# jmb575.net
KiCad netlist of a schematic drawn in Altium Designer
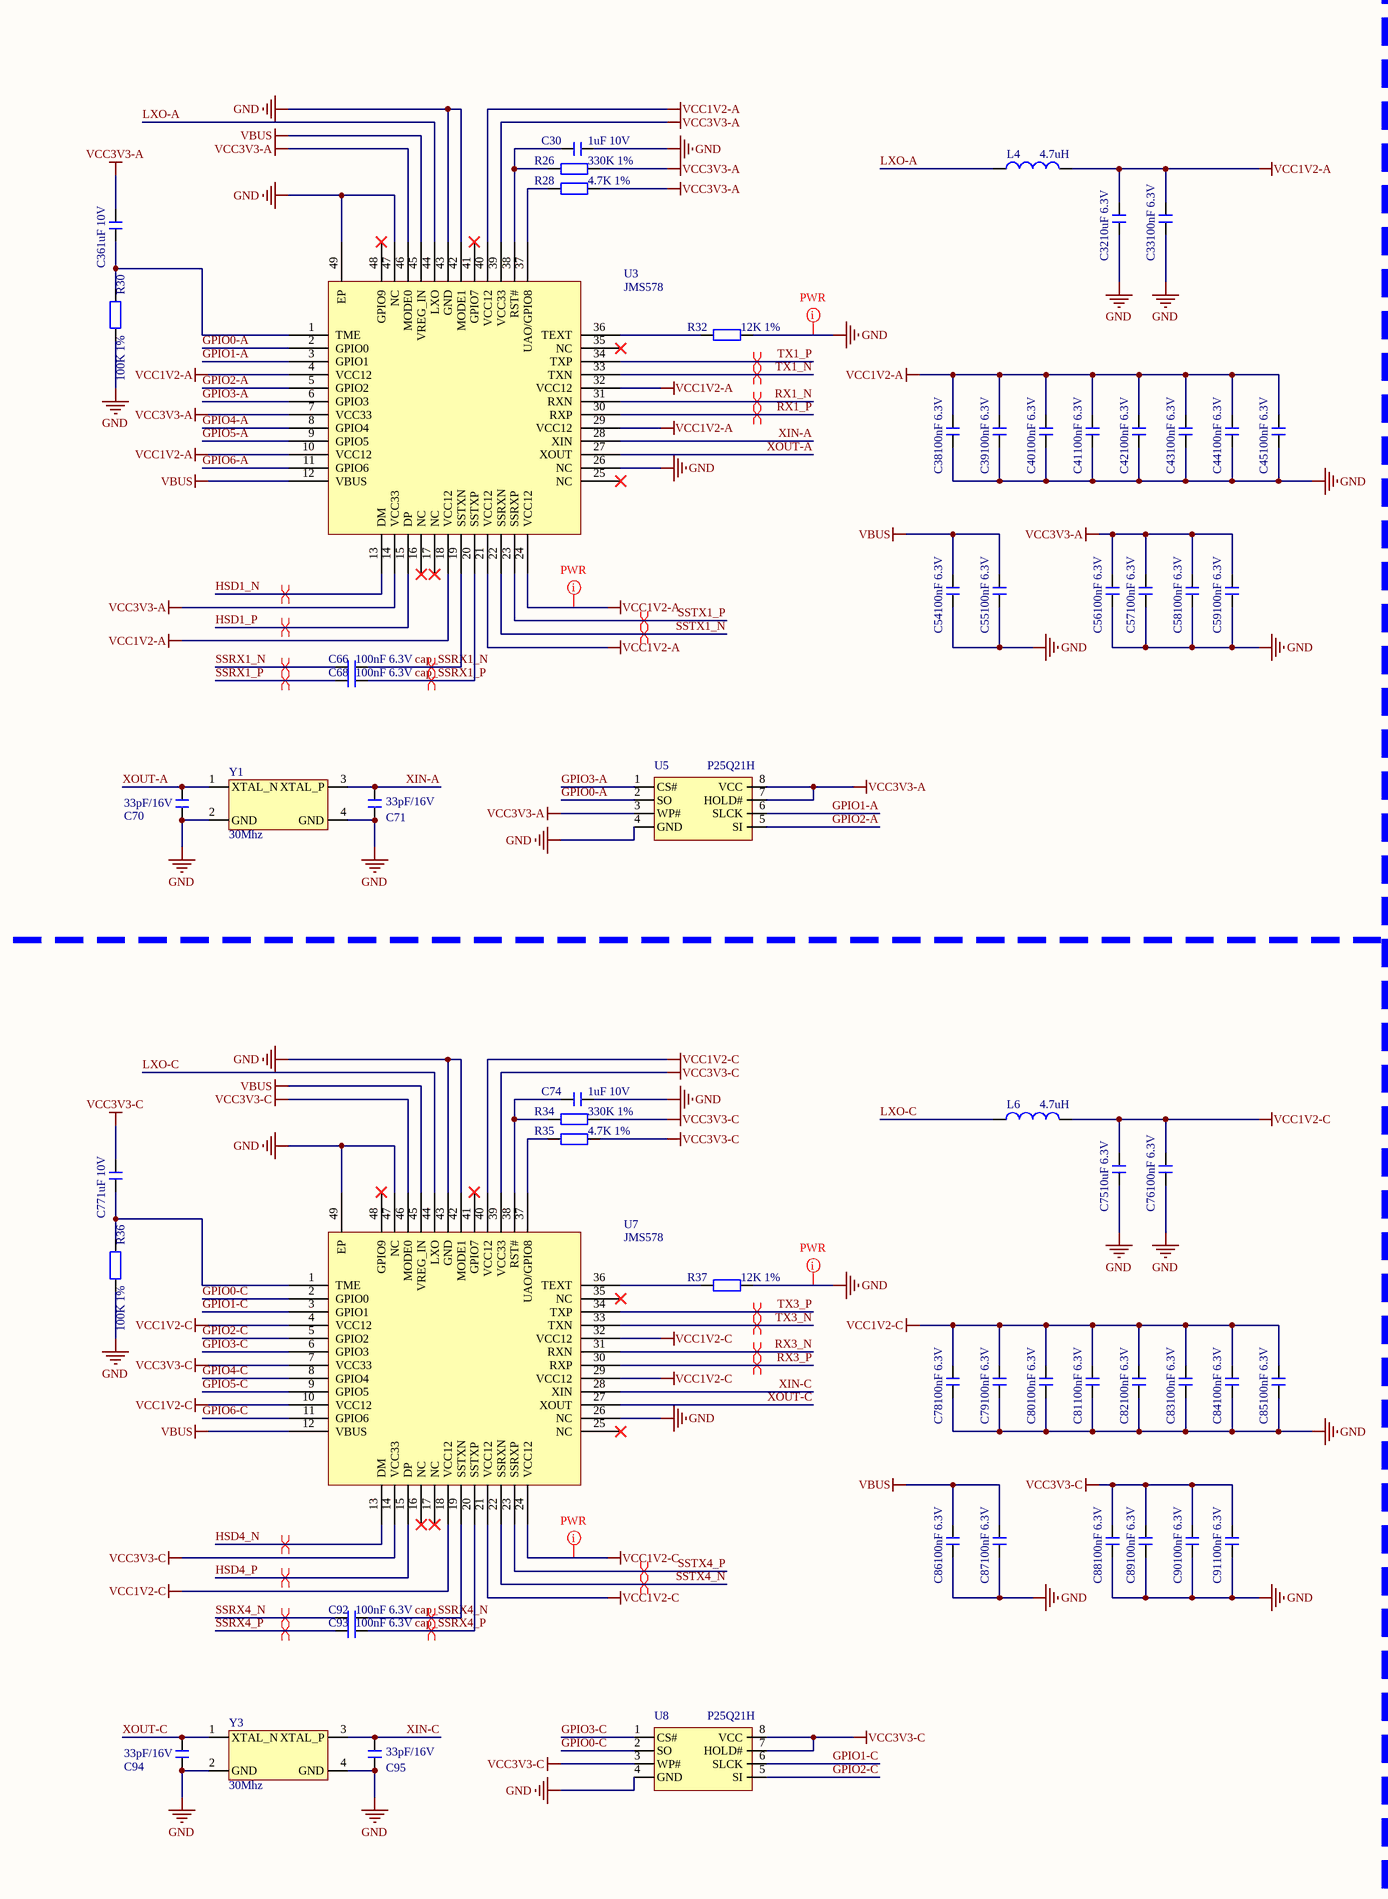
[diagram p0: jmb575.SchDoc, left]
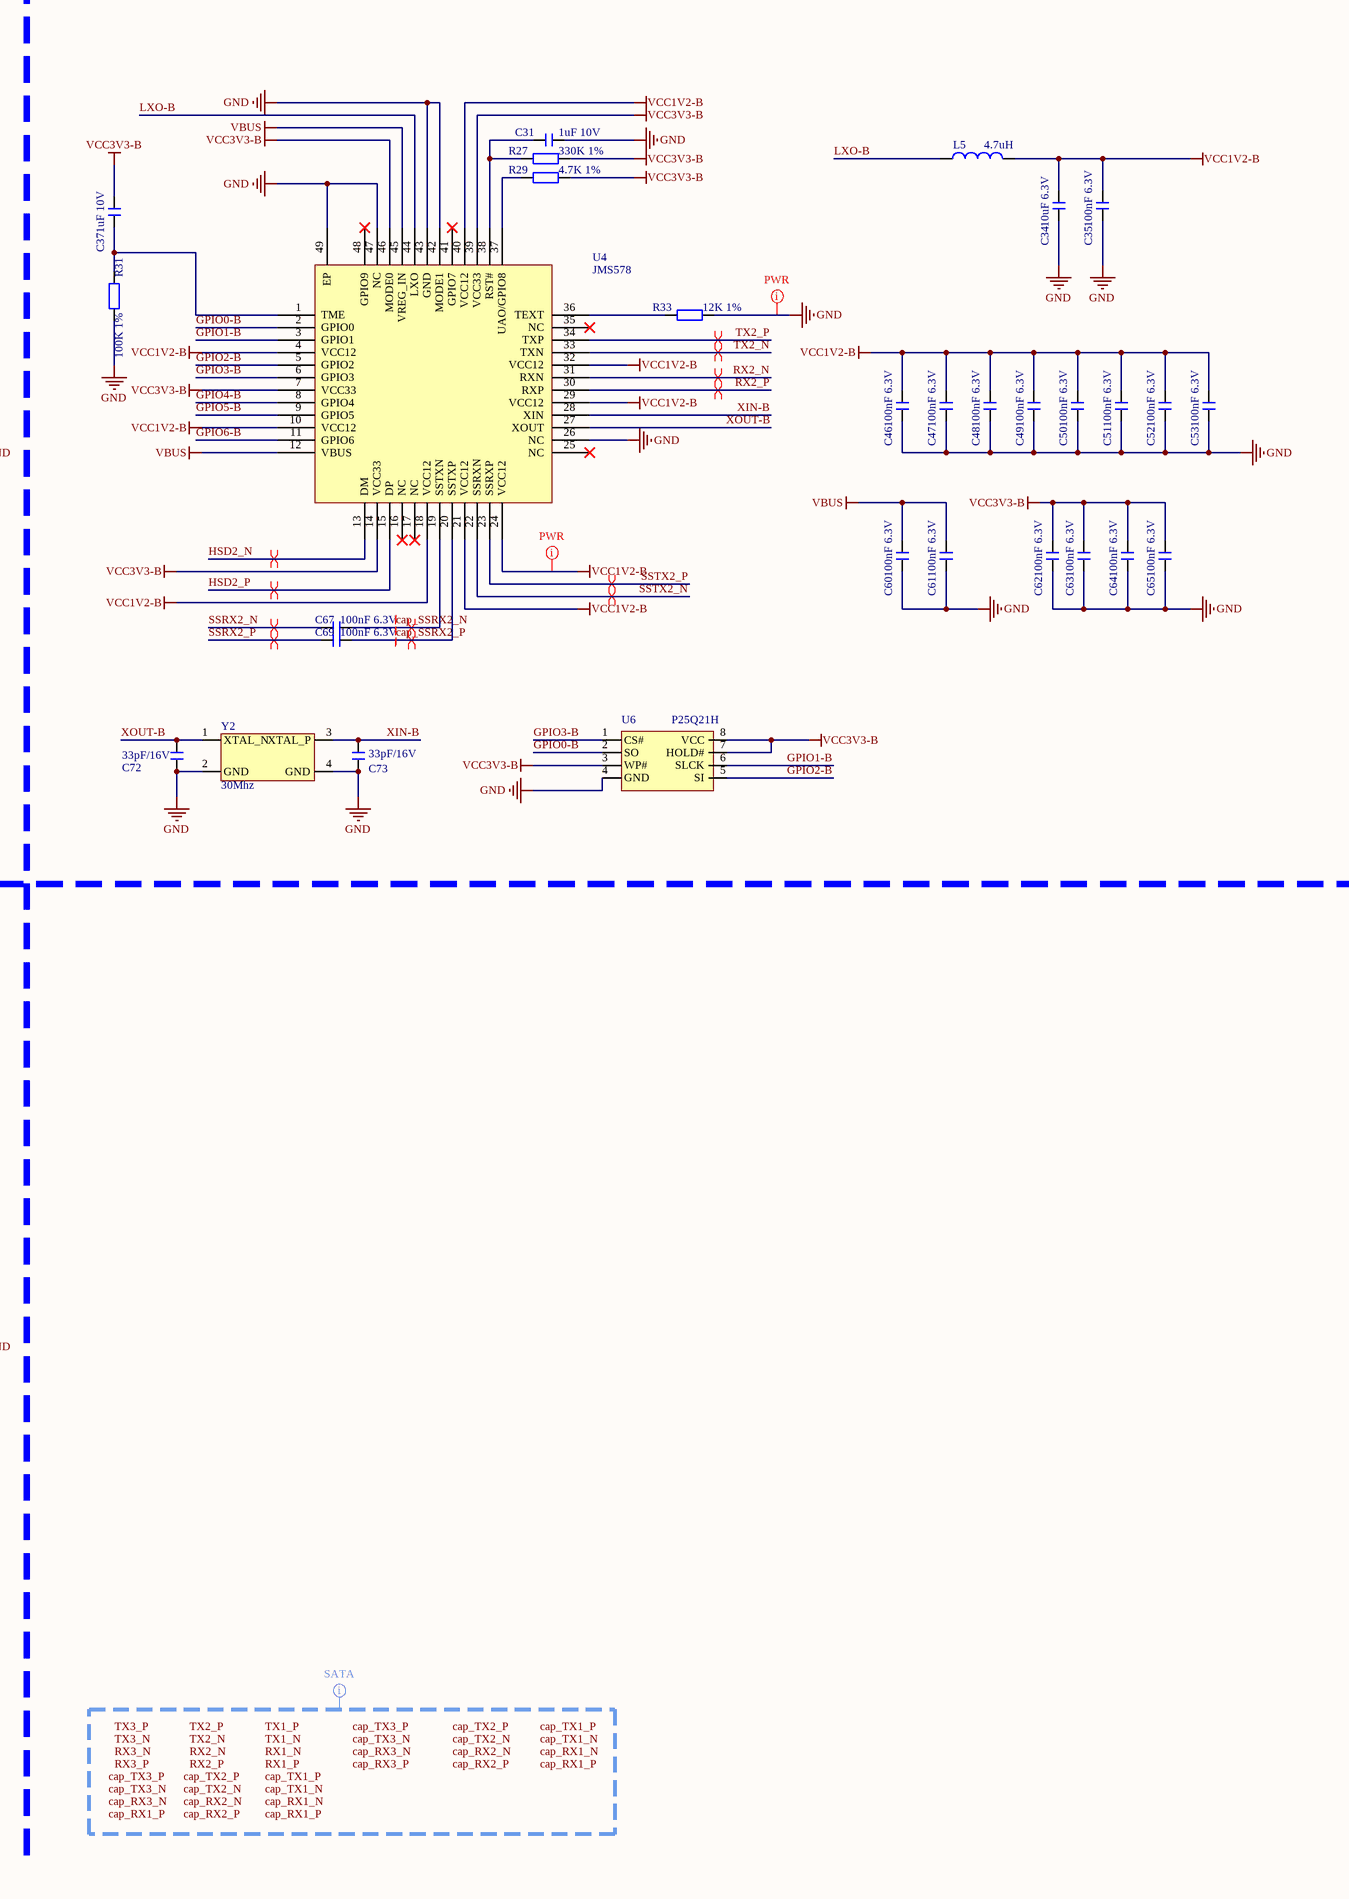
[diagram p1: jmb575.SchDoc, right]

(export (version "E")
  (design (tool "Eeschema 10.0.6"))
  (components
    (comp (ref "C30")
      (value "1uF 10V")
      (footprint "C0402_L")
      (description "无极性贴片电容")
      (fields (field (name "版权归属") "源创客"))
      (libsource (lib "Capacitor") (part "C"))
    )
    (comp (ref "C31")
      (value "1uF 10V")
      (footprint "C0402_L")
      (description "无极性贴片电容")
      (fields (field (name "版权归属") "源创客"))
      (libsource (lib "Capacitor") (part "C"))
    )
    (comp (ref "C32")
      (value "10uF 6.3V")
      (footprint "C0603_L")
      (description "无极性贴片电容")
      (fields (field (name "版权归属") "源创客"))
      (libsource (lib "Capacitor") (part "C"))
    )
    (comp (ref "C33")
      (value "100nF 6.3V")
      (footprint "C0402_L")
      (description "无极性贴片电容")
      (fields (field (name "版权归属") "源创客"))
      (libsource (lib "Capacitor") (part "C"))
    )
    (comp (ref "C34")
      (value "10uF 6.3V")
      (footprint "C0603_L")
      (description "无极性贴片电容")
      (fields (field (name "版权归属") "源创客"))
      (libsource (lib "Capacitor") (part "C"))
    )
    (comp (ref "C35")
      (value "100nF 6.3V")
      (footprint "C0402_L")
      (description "无极性贴片电容")
      (fields (field (name "版权归属") "源创客"))
      (libsource (lib "Capacitor") (part "C"))
    )
    (comp (ref "C36")
      (value "1uF 10V")
      (footprint "C0402_L")
      (description "无极性贴片电容")
      (fields (field (name "版权归属") "源创客"))
      (libsource (lib "Capacitor") (part "C"))
    )
    (comp (ref "C37")
      (value "1uF 10V")
      (footprint "C0402_L")
      (description "无极性贴片电容")
      (fields (field (name "版权归属") "源创客"))
      (libsource (lib "Capacitor") (part "C"))
    )
    (comp (ref "C38")
      (value "100nF 6.3V")
      (footprint "C0402_L")
      (description "无极性贴片电容")
      (fields (field (name "版权归属") "源创客"))
      (libsource (lib "Capacitor") (part "C"))
    )
    (comp (ref "C39")
      (value "100nF 6.3V")
      (footprint "C0402_L")
      (description "无极性贴片电容")
      (fields (field (name "版权归属") "源创客"))
      (libsource (lib "Capacitor") (part "C"))
    )
    (comp (ref "C40")
      (value "100nF 6.3V")
      (footprint "C0402_L")
      (description "无极性贴片电容")
      (fields (field (name "版权归属") "源创客"))
      (libsource (lib "Capacitor") (part "C"))
    )
    (comp (ref "C41")
      (value "100nF 6.3V")
      (footprint "C0402_L")
      (description "无极性贴片电容")
      (fields (field (name "版权归属") "源创客"))
      (libsource (lib "Capacitor") (part "C"))
    )
    (comp (ref "C42")
      (value "100nF 6.3V")
      (footprint "C0402_L")
      (description "无极性贴片电容")
      (fields (field (name "版权归属") "源创客"))
      (libsource (lib "Capacitor") (part "C"))
    )
    (comp (ref "C43")
      (value "100nF 6.3V")
      (footprint "C0402_L")
      (description "无极性贴片电容")
      (fields (field (name "版权归属") "源创客"))
      (libsource (lib "Capacitor") (part "C"))
    )
    (comp (ref "C44")
      (value "100nF 6.3V")
      (footprint "C0402_L")
      (description "无极性贴片电容")
      (fields (field (name "版权归属") "源创客"))
      (libsource (lib "Capacitor") (part "C"))
    )
    (comp (ref "C45")
      (value "100nF 6.3V")
      (footprint "C0402_L")
      (description "无极性贴片电容")
      (fields (field (name "版权归属") "源创客"))
      (libsource (lib "Capacitor") (part "C"))
    )
    (comp (ref "C46")
      (value "100nF 6.3V")
      (footprint "C0402_L")
      (description "无极性贴片电容")
      (fields (field (name "版权归属") "源创客"))
      (libsource (lib "Capacitor") (part "C"))
    )
    (comp (ref "C47")
      (value "100nF 6.3V")
      (footprint "C0402_L")
      (description "无极性贴片电容")
      (fields (field (name "版权归属") "源创客"))
      (libsource (lib "Capacitor") (part "C"))
    )
    (comp (ref "C48")
      (value "100nF 6.3V")
      (footprint "C0402_L")
      (description "无极性贴片电容")
      (fields (field (name "版权归属") "源创客"))
      (libsource (lib "Capacitor") (part "C"))
    )
    (comp (ref "C49")
      (value "100nF 6.3V")
      (footprint "C0402_L")
      (description "无极性贴片电容")
      (fields (field (name "版权归属") "源创客"))
      (libsource (lib "Capacitor") (part "C"))
    )
    (comp (ref "C50")
      (value "100nF 6.3V")
      (footprint "C0402_L")
      (description "无极性贴片电容")
      (fields (field (name "版权归属") "源创客"))
      (libsource (lib "Capacitor") (part "C"))
    )
    (comp (ref "C51")
      (value "100nF 6.3V")
      (footprint "C0402_L")
      (description "无极性贴片电容")
      (fields (field (name "版权归属") "源创客"))
      (libsource (lib "Capacitor") (part "C"))
    )
    (comp (ref "C52")
      (value "100nF 6.3V")
      (footprint "C0402_L")
      (description "无极性贴片电容")
      (fields (field (name "版权归属") "源创客"))
      (libsource (lib "Capacitor") (part "C"))
    )
    (comp (ref "C53")
      (value "100nF 6.3V")
      (footprint "C0402_L")
      (description "无极性贴片电容")
      (fields (field (name "版权归属") "源创客"))
      (libsource (lib "Capacitor") (part "C"))
    )
    (comp (ref "C54")
      (value "100nF 6.3V")
      (footprint "C0402_L")
      (description "无极性贴片电容")
      (fields (field (name "版权归属") "源创客"))
      (libsource (lib "Capacitor") (part "C"))
    )
    (comp (ref "C55")
      (value "100nF 6.3V")
      (footprint "C0402_L")
      (description "无极性贴片电容")
      (fields (field (name "版权归属") "源创客"))
      (libsource (lib "Capacitor") (part "C"))
    )
    (comp (ref "C56")
      (value "100nF 6.3V")
      (footprint "C0402_L")
      (description "无极性贴片电容")
      (fields (field (name "版权归属") "源创客"))
      (libsource (lib "Capacitor") (part "C"))
    )
    (comp (ref "C57")
      (value "100nF 6.3V")
      (footprint "C0402_L")
      (description "无极性贴片电容")
      (fields (field (name "版权归属") "源创客"))
      (libsource (lib "Capacitor") (part "C"))
    )
    (comp (ref "C58")
      (value "100nF 6.3V")
      (footprint "C0402_L")
      (description "无极性贴片电容")
      (fields (field (name "版权归属") "源创客"))
      (libsource (lib "Capacitor") (part "C"))
    )
    (comp (ref "C59")
      (value "100nF 6.3V")
      (footprint "C0402_L")
      (description "无极性贴片电容")
      (fields (field (name "版权归属") "源创客"))
      (libsource (lib "Capacitor") (part "C"))
    )
    (comp (ref "C60")
      (value "100nF 6.3V")
      (footprint "C0402_L")
      (description "无极性贴片电容")
      (fields (field (name "版权归属") "源创客"))
      (libsource (lib "Capacitor") (part "C"))
    )
    (comp (ref "C61")
      (value "100nF 6.3V")
      (footprint "C0402_L")
      (description "无极性贴片电容")
      (fields (field (name "版权归属") "源创客"))
      (libsource (lib "Capacitor") (part "C"))
    )
    (comp (ref "C62")
      (value "100nF 6.3V")
      (footprint "C0402_L")
      (description "无极性贴片电容")
      (fields (field (name "版权归属") "源创客"))
      (libsource (lib "Capacitor") (part "C"))
    )
    (comp (ref "C63")
      (value "100nF 6.3V")
      (footprint "C0402_L")
      (description "无极性贴片电容")
      (fields (field (name "版权归属") "源创客"))
      (libsource (lib "Capacitor") (part "C"))
    )
    (comp (ref "C64")
      (value "100nF 6.3V")
      (footprint "C0402_L")
      (description "无极性贴片电容")
      (fields (field (name "版权归属") "源创客"))
      (libsource (lib "Capacitor") (part "C"))
    )
    (comp (ref "C65")
      (value "100nF 6.3V")
      (footprint "C0402_L")
      (description "无极性贴片电容")
      (fields (field (name "版权归属") "源创客"))
      (libsource (lib "Capacitor") (part "C"))
    )
    (comp (ref "C66")
      (value "100nF 6.3V")
      (footprint "C0402_L")
      (description "无极性贴片电容")
      (fields (field (name "版权归属") "源创客"))
      (libsource (lib "Capacitor") (part "C"))
    )
    (comp (ref "C67")
      (value "100nF 6.3V")
      (footprint "C0402_L")
      (description "无极性贴片电容")
      (fields (field (name "版权归属") "源创客"))
      (libsource (lib "Capacitor") (part "C"))
    )
    (comp (ref "C68")
      (value "100nF 6.3V")
      (footprint "C0402_L")
      (description "无极性贴片电容")
      (fields (field (name "版权归属") "源创客"))
      (libsource (lib "Capacitor") (part "C"))
    )
    (comp (ref "C69")
      (value "100nF 6.3V")
      (footprint "C0402_L")
      (description "无极性贴片电容")
      (fields (field (name "版权归属") "源创客"))
      (libsource (lib "Capacitor") (part "C"))
    )
    (comp (ref "C70")
      (value "33pF/16V")
      (footprint "C0402_L")
      (description "无极性贴片电容")
      (fields (field (name "版权归属") "源创客"))
      (libsource (lib "Capacitor") (part "C"))
    )
    (comp (ref "C71")
      (value "33pF/16V")
      (footprint "C0402_L")
      (description "无极性贴片电容")
      (fields (field (name "版权归属") "源创客"))
      (libsource (lib "Capacitor") (part "C"))
    )
    (comp (ref "C72")
      (value "33pF/16V")
      (footprint "C0402_L")
      (description "无极性贴片电容")
      (fields (field (name "版权归属") "源创客"))
      (libsource (lib "Capacitor") (part "C"))
    )
    (comp (ref "C73")
      (value "33pF/16V")
      (footprint "C0402_L")
      (description "无极性贴片电容")
      (fields (field (name "版权归属") "源创客"))
      (libsource (lib "Capacitor") (part "C"))
    )
    (comp (ref "C74")
      (value "1uF 10V")
      (footprint "C0402_L")
      (description "无极性贴片电容")
      (fields (field (name "版权归属") "源创客"))
      (libsource (lib "Capacitor") (part "C"))
    )
    (comp (ref "C75")
      (value "10uF 6.3V")
      (footprint "C0603_L")
      (description "无极性贴片电容")
      (fields (field (name "版权归属") "源创客"))
      (libsource (lib "Capacitor") (part "C"))
    )
    (comp (ref "C76")
      (value "100nF 6.3V")
      (footprint "C0402_L")
      (description "无极性贴片电容")
      (fields (field (name "版权归属") "源创客"))
      (libsource (lib "Capacitor") (part "C"))
    )
    (comp (ref "C77")
      (value "1uF 10V")
      (footprint "C0402_L")
      (description "无极性贴片电容")
      (fields (field (name "版权归属") "源创客"))
      (libsource (lib "Capacitor") (part "C"))
    )
    (comp (ref "C78")
      (value "100nF 6.3V")
      (footprint "C0402_L")
      (description "无极性贴片电容")
      (fields (field (name "版权归属") "源创客"))
      (libsource (lib "Capacitor") (part "C"))
    )
    (comp (ref "C79")
      (value "100nF 6.3V")
      (footprint "C0402_L")
      (description "无极性贴片电容")
      (fields (field (name "版权归属") "源创客"))
      (libsource (lib "Capacitor") (part "C"))
    )
    (comp (ref "C80")
      (value "100nF 6.3V")
      (footprint "C0402_L")
      (description "无极性贴片电容")
      (fields (field (name "版权归属") "源创客"))
      (libsource (lib "Capacitor") (part "C"))
    )
    (comp (ref "C81")
      (value "100nF 6.3V")
      (footprint "C0402_L")
      (description "无极性贴片电容")
      (fields (field (name "版权归属") "源创客"))
      (libsource (lib "Capacitor") (part "C"))
    )
    (comp (ref "C82")
      (value "100nF 6.3V")
      (footprint "C0402_L")
      (description "无极性贴片电容")
      (fields (field (name "版权归属") "源创客"))
      (libsource (lib "Capacitor") (part "C"))
    )
    (comp (ref "C83")
      (value "100nF 6.3V")
      (footprint "C0402_L")
      (description "无极性贴片电容")
      (fields (field (name "版权归属") "源创客"))
      (libsource (lib "Capacitor") (part "C"))
    )
    (comp (ref "C84")
      (value "100nF 6.3V")
      (footprint "C0402_L")
      (description "无极性贴片电容")
      (fields (field (name "版权归属") "源创客"))
      (libsource (lib "Capacitor") (part "C"))
    )
    (comp (ref "C85")
      (value "100nF 6.3V")
      (footprint "C0402_L")
      (description "无极性贴片电容")
      (fields (field (name "版权归属") "源创客"))
      (libsource (lib "Capacitor") (part "C"))
    )
    (comp (ref "C86")
      (value "100nF 6.3V")
      (footprint "C0402_L")
      (description "无极性贴片电容")
      (fields (field (name "版权归属") "源创客"))
      (libsource (lib "Capacitor") (part "C"))
    )
    (comp (ref "C87")
      (value "100nF 6.3V")
      (footprint "C0402_L")
      (description "无极性贴片电容")
      (fields (field (name "版权归属") "源创客"))
      (libsource (lib "Capacitor") (part "C"))
    )
    (comp (ref "C88")
      (value "100nF 6.3V")
      (footprint "C0402_L")
      (description "无极性贴片电容")
      (fields (field (name "版权归属") "源创客"))
      (libsource (lib "Capacitor") (part "C"))
    )
    (comp (ref "C89")
      (value "100nF 6.3V")
      (footprint "C0402_L")
      (description "无极性贴片电容")
      (fields (field (name "版权归属") "源创客"))
      (libsource (lib "Capacitor") (part "C"))
    )
    (comp (ref "C90")
      (value "100nF 6.3V")
      (footprint "C0402_L")
      (description "无极性贴片电容")
      (fields (field (name "版权归属") "源创客"))
      (libsource (lib "Capacitor") (part "C"))
    )
    (comp (ref "C91")
      (value "100nF 6.3V")
      (footprint "C0402_L")
      (description "无极性贴片电容")
      (fields (field (name "版权归属") "源创客"))
      (libsource (lib "Capacitor") (part "C"))
    )
    (comp (ref "C92")
      (value "100nF 6.3V")
      (footprint "C0402_L")
      (description "无极性贴片电容")
      (fields (field (name "版权归属") "源创客"))
      (libsource (lib "Capacitor") (part "C"))
    )
    (comp (ref "C93")
      (value "100nF 6.3V")
      (footprint "C0402_L")
      (description "无极性贴片电容")
      (fields (field (name "版权归属") "源创客"))
      (libsource (lib "Capacitor") (part "C"))
    )
    (comp (ref "C94")
      (value "33pF/16V")
      (footprint "C0402_L")
      (description "无极性贴片电容")
      (fields (field (name "版权归属") "源创客"))
      (libsource (lib "Capacitor") (part "C"))
    )
    (comp (ref "C95")
      (value "33pF/16V")
      (footprint "C0402_L")
      (description "无极性贴片电容")
      (fields (field (name "版权归属") "源创客"))
      (libsource (lib "Capacitor") (part "C"))
    )
    (comp (ref "L4")
      (value "4.7uH")
      (footprint "SMMS0420")
      (description "小功率贴片电感")
      (fields (field (name "版权归属") "源创客"))
      (libsource (lib "Inductor") (part "L"))
    )
    (comp (ref "L5")
      (value "4.7uH")
      (footprint "SMMS0420")
      (description "小功率贴片电感")
      (fields (field (name "版权归属") "源创客"))
      (libsource (lib "Inductor") (part "L"))
    )
    (comp (ref "L6")
      (value "4.7uH")
      (footprint "SMMS0420")
      (description "小功率贴片电感")
      (fields (field (name "版权归属") "源创客"))
      (libsource (lib "Inductor") (part "L"))
    )
    (comp (ref "R26")
      (value "330K 1%")
      (footprint "R0402_L")
      (description "贴片电阻")
      (fields (field (name "版权归属") "源创客"))
      (libsource (lib "Resistor") (part "R"))
    )
    (comp (ref "R27")
      (value "330K 1%")
      (footprint "R0402_L")
      (description "贴片电阻")
      (fields (field (name "版权归属") "源创客"))
      (libsource (lib "Resistor") (part "R"))
    )
    (comp (ref "R28")
      (value "4.7K 1%")
      (footprint "R0402_L")
      (description "贴片电阻")
      (fields (field (name "版权归属") "源创客"))
      (libsource (lib "Resistor") (part "R"))
    )
    (comp (ref "R29")
      (value "4.7K 1%")
      (footprint "R0402_L")
      (description "贴片电阻")
      (fields (field (name "版权归属") "源创客"))
      (libsource (lib "Resistor") (part "R"))
    )
    (comp (ref "R30")
      (value "100K 1%")
      (footprint "R0402_L")
      (description "贴片电阻")
      (fields (field (name "版权归属") "源创客"))
      (libsource (lib "Resistor") (part "R"))
    )
    (comp (ref "R31")
      (value "100K 1%")
      (footprint "R0402_L")
      (description "贴片电阻")
      (fields (field (name "版权归属") "源创客"))
      (libsource (lib "Resistor") (part "R"))
    )
    (comp (ref "R32")
      (value "12K 1%")
      (footprint "R0402_L")
      (description "贴片电阻")
      (fields (field (name "版权归属") "源创客"))
      (libsource (lib "Resistor") (part "R"))
    )
    (comp (ref "R33")
      (value "12K 1%")
      (footprint "R0402_L")
      (description "贴片电阻")
      (fields (field (name "版权归属") "源创客"))
      (libsource (lib "Resistor") (part "R"))
    )
    (comp (ref "R34")
      (value "330K 1%")
      (footprint "R0402_L")
      (description "贴片电阻")
      (fields (field (name "版权归属") "源创客"))
      (libsource (lib "Resistor") (part "R"))
    )
    (comp (ref "R35")
      (value "4.7K 1%")
      (footprint "R0402_L")
      (description "贴片电阻")
      (fields (field (name "版权归属") "源创客"))
      (libsource (lib "Resistor") (part "R"))
    )
    (comp (ref "R36")
      (value "100K 1%")
      (footprint "R0402_L")
      (description "贴片电阻")
      (fields (field (name "版权归属") "源创客"))
      (libsource (lib "Resistor") (part "R"))
    )
    (comp (ref "R37")
      (value "12K 1%")
      (footprint "R0402_L")
      (description "贴片电阻")
      (fields (field (name "版权归属") "源创客"))
      (libsource (lib "Resistor") (part "R"))
    )
    (comp (ref "U3")
      (value "JMS578")
      (footprint "QFN48-L6.0-W6.0-P0.4")
      (libsource (lib "Brage") (part "JMS578"))
    )
    (comp (ref "U4")
      (value "JMS578")
      (footprint "QFN48-L6.0-W6.0-P0.4")
      (libsource (lib "Brage") (part "JMS578"))
    )
    (comp (ref "U5") (value "P25Q21H") (footprint "SOP8_L") (libsource (lib "Flash") (part "P25D40H")))
    (comp (ref "U6") (value "P25Q21H") (footprint "SOP8_L") (libsource (lib "Flash") (part "P25D40H")))
    (comp (ref "U7")
      (value "JMS578")
      (footprint "QFN48-L6.0-W6.0-P0.4")
      (libsource (lib "Brage") (part "JMS578"))
    )
    (comp (ref "U8") (value "P25Q21H") (footprint "SOP8_L") (libsource (lib "Flash") (part "P25D40H")))
    (comp (ref "Y1") (value "30Mhz") (footprint "OSC 3225-4P") (libsource (lib "Crystal") (part "Crystal")))
    (comp (ref "Y2") (value "30Mhz") (footprint "OSC 3225-4P") (libsource (lib "Crystal") (part "Crystal")))
    (comp (ref "Y3") (value "30Mhz") (footprint "OSC 3225-4P") (libsource (lib "Crystal") (part "Crystal")))
  )
  (nets
    (net (code "1") (name "/GPIO0-A") (class "Default")
      (node (ref "U3") (pin "2") (pinfunction "GPIO0_2") (pintype "passive"))
      (node (ref "U5") (pin "2") (pinfunction "SO_2") (pintype "passive"))
    )
    (net (code "2") (name "/GPIO0-B") (class "Default")
      (node (ref "U4") (pin "2") (pinfunction "GPIO0_2") (pintype "passive"))
      (node (ref "U6") (pin "2") (pinfunction "SO_2") (pintype "passive"))
    )
    (net (code "3") (name "/GPIO0-C") (class "Default")
      (node (ref "U7") (pin "2") (pinfunction "GPIO0_2") (pintype "passive"))
      (node (ref "U8") (pin "2") (pinfunction "SO_2") (pintype "passive"))
    )
    (net (code "4") (name "/GPIO1-A") (class "Default")
      (node (ref "U3") (pin "3") (pinfunction "GPIO1_3") (pintype "passive"))
      (node (ref "U5") (pin "6") (pinfunction "SLCK_6") (pintype "passive"))
    )
    (net (code "5") (name "/GPIO1-B") (class "Default")
      (node (ref "U4") (pin "3") (pinfunction "GPIO1_3") (pintype "passive"))
      (node (ref "U6") (pin "6") (pinfunction "SLCK_6") (pintype "passive"))
    )
    (net (code "6") (name "/GPIO1-C") (class "Default")
      (node (ref "U7") (pin "3") (pinfunction "GPIO1_3") (pintype "passive"))
      (node (ref "U8") (pin "6") (pinfunction "SLCK_6") (pintype "passive"))
    )
    (net (code "7") (name "/GPIO2-A") (class "Default")
      (node (ref "U3") (pin "5") (pinfunction "GPIO2_5") (pintype "passive"))
      (node (ref "U5") (pin "5") (pinfunction "SI_5") (pintype "passive"))
    )
    (net (code "8") (name "/GPIO2-B") (class "Default")
      (node (ref "U4") (pin "5") (pinfunction "GPIO2_5") (pintype "passive"))
      (node (ref "U6") (pin "5") (pinfunction "SI_5") (pintype "passive"))
    )
    (net (code "9") (name "/GPIO2-C") (class "Default")
      (node (ref "U7") (pin "5") (pinfunction "GPIO2_5") (pintype "passive"))
      (node (ref "U8") (pin "5") (pinfunction "SI_5") (pintype "passive"))
    )
    (net (code "10") (name "/GPIO3-A") (class "Default")
      (node (ref "U3") (pin "6") (pinfunction "GPIO3_6") (pintype "passive"))
      (node (ref "U5") (pin "1") (pinfunction "CS#_1") (pintype "passive"))
    )
    (net (code "11") (name "/GPIO3-B") (class "Default")
      (node (ref "U4") (pin "6") (pinfunction "GPIO3_6") (pintype "passive"))
      (node (ref "U6") (pin "1") (pinfunction "CS#_1") (pintype "passive"))
    )
    (net (code "12") (name "/GPIO3-C") (class "Default")
      (node (ref "U7") (pin "6") (pinfunction "GPIO3_6") (pintype "passive"))
      (node (ref "U8") (pin "1") (pinfunction "CS#_1") (pintype "passive"))
    )
    (net (code "13") (name "/GPIO4-A") (class "Default")
      (node (ref "U3") (pin "8") (pinfunction "GPIO4_8") (pintype "passive"))
    )
    (net (code "14") (name "/GPIO4-B") (class "Default")
      (node (ref "U4") (pin "8") (pinfunction "GPIO4_8") (pintype "passive"))
    )
    (net (code "15") (name "/GPIO4-C") (class "Default")
      (node (ref "U7") (pin "8") (pinfunction "GPIO4_8") (pintype "passive"))
    )
    (net (code "16") (name "/GPIO5-A") (class "Default")
      (node (ref "U3") (pin "9") (pinfunction "GPIO5_9") (pintype "passive"))
    )
    (net (code "17") (name "/GPIO5-B") (class "Default")
      (node (ref "U4") (pin "9") (pinfunction "GPIO5_9") (pintype "passive"))
    )
    (net (code "18") (name "/GPIO5-C") (class "Default")
      (node (ref "U7") (pin "9") (pinfunction "GPIO5_9") (pintype "passive"))
    )
    (net (code "19") (name "/GPIO6-A") (class "Default")
      (node (ref "U3") (pin "11") (pinfunction "GPIO6_11") (pintype "passive"))
    )
    (net (code "20") (name "/GPIO6-B") (class "Default")
      (node (ref "U4") (pin "11") (pinfunction "GPIO6_11") (pintype "passive"))
    )
    (net (code "21") (name "/GPIO6-C") (class "Default")
      (node (ref "U7") (pin "11") (pinfunction "GPIO6_11") (pintype "passive"))
    )
    (net (code "22") (name "/HSD1_N") (class "Default")
      (node (ref "U3") (pin "13") (pinfunction "DM_13") (pintype "passive"))
    )
    (net (code "23") (name "/HSD1_P") (class "Default")
      (node (ref "U3") (pin "15") (pinfunction "DP_15") (pintype "passive"))
    )
    (net (code "24") (name "/HSD2_N") (class "Default")
      (node (ref "U4") (pin "13") (pinfunction "DM_13") (pintype "passive"))
    )
    (net (code "25") (name "/HSD2_P") (class "Default")
      (node (ref "U4") (pin "15") (pinfunction "DP_15") (pintype "passive"))
    )
    (net (code "26") (name "/HSD4_N") (class "Default")
      (node (ref "U7") (pin "13") (pinfunction "DM_13") (pintype "passive"))
    )
    (net (code "27") (name "/HSD4_P") (class "Default")
      (node (ref "U7") (pin "15") (pinfunction "DP_15") (pintype "passive"))
    )
    (net (code "28") (name "/LXO-A") (class "Default")
      (node (ref "L4") (pin "1") (pinfunction "1_1") (pintype "passive"))
      (node (ref "U3") (pin "44") (pinfunction "LXO_44") (pintype "passive"))
    )
    (net (code "29") (name "/LXO-B") (class "Default")
      (node (ref "L5") (pin "1") (pinfunction "1_1") (pintype "passive"))
      (node (ref "U4") (pin "44") (pinfunction "LXO_44") (pintype "passive"))
    )
    (net (code "30") (name "/LXO-C") (class "Default")
      (node (ref "L6") (pin "1") (pinfunction "1_1") (pintype "passive"))
      (node (ref "U7") (pin "44") (pinfunction "LXO_44") (pintype "passive"))
    )
    (net (code "31") (name "/RX1_N") (class "Default")
      (node (ref "U3") (pin "31") (pinfunction "RXN_31") (pintype "passive"))
    )
    (net (code "32") (name "/RX1_P") (class "Default")
      (node (ref "U3") (pin "30") (pinfunction "RXP_30") (pintype "passive"))
    )
    (net (code "33") (name "/RX2_N") (class "Default")
      (node (ref "U4") (pin "31") (pinfunction "RXN_31") (pintype "passive"))
    )
    (net (code "34") (name "/RX2_P") (class "Default")
      (node (ref "U4") (pin "30") (pinfunction "RXP_30") (pintype "passive"))
    )
    (net (code "35") (name "/RX3_N") (class "Default")
      (node (ref "U7") (pin "31") (pinfunction "RXN_31") (pintype "passive"))
    )
    (net (code "36") (name "/RX3_P") (class "Default")
      (node (ref "U7") (pin "30") (pinfunction "RXP_30") (pintype "passive"))
    )
    (net (code "37") (name "/SSRX1_N") (class "Default")
      (node (ref "C66") (pin "1") (pinfunction "1_1") (pintype "passive"))
    )
    (net (code "38") (name "/SSRX1_P") (class "Default")
      (node (ref "C68") (pin "1") (pinfunction "1_1") (pintype "passive"))
    )
    (net (code "39") (name "/SSRX2_N") (class "Default")
      (node (ref "C67") (pin "1") (pinfunction "1_1") (pintype "passive"))
    )
    (net (code "40") (name "/SSRX2_P") (class "Default")
      (node (ref "C69") (pin "1") (pinfunction "1_1") (pintype "passive"))
    )
    (net (code "41") (name "/SSRX4_N") (class "Default")
      (node (ref "C92") (pin "1") (pinfunction "1_1") (pintype "passive"))
    )
    (net (code "42") (name "/SSRX4_P") (class "Default")
      (node (ref "C93") (pin "1") (pinfunction "1_1") (pintype "passive"))
    )
    (net (code "43") (name "/SSTX1_N") (class "Default")
      (node (ref "U3") (pin "22") (pinfunction "SSRXN_22") (pintype "passive"))
    )
    (net (code "44") (name "/SSTX1_P") (class "Default")
      (node (ref "U3") (pin "23") (pinfunction "SSRXP_23") (pintype "passive"))
    )
    (net (code "45") (name "/SSTX2_N") (class "Default")
      (node (ref "U4") (pin "22") (pinfunction "SSRXN_22") (pintype "passive"))
    )
    (net (code "46") (name "/SSTX2_P") (class "Default")
      (node (ref "U4") (pin "23") (pinfunction "SSRXP_23") (pintype "passive"))
    )
    (net (code "47") (name "/SSTX4_N") (class "Default")
      (node (ref "U7") (pin "22") (pinfunction "SSRXN_22") (pintype "passive"))
    )
    (net (code "48") (name "/SSTX4_P") (class "Default")
      (node (ref "U7") (pin "23") (pinfunction "SSRXP_23") (pintype "passive"))
    )
    (net (code "49") (name "/TX1_N") (class "Default")
      (node (ref "U3") (pin "33") (pinfunction "TXN_33") (pintype "passive"))
    )
    (net (code "50") (name "/TX1_P") (class "Default")
      (node (ref "U3") (pin "34") (pinfunction "TXP_34") (pintype "passive"))
    )
    (net (code "51") (name "/TX2_N") (class "Default")
      (node (ref "U4") (pin "33") (pinfunction "TXN_33") (pintype "passive"))
    )
    (net (code "52") (name "/TX2_P") (class "Default")
      (node (ref "U4") (pin "34") (pinfunction "TXP_34") (pintype "passive"))
    )
    (net (code "53") (name "/TX3_N") (class "Default")
      (node (ref "U7") (pin "33") (pinfunction "TXN_33") (pintype "passive"))
    )
    (net (code "54") (name "/TX3_P") (class "Default")
      (node (ref "U7") (pin "34") (pinfunction "TXP_34") (pintype "passive"))
    )
    (net (code "55") (name "/XIN-A") (class "Default")
      (node (ref "C71") (pin "1") (pinfunction "1_1") (pintype "passive"))
      (node (ref "U3") (pin "28") (pinfunction "XIN_28") (pintype "passive"))
      (node (ref "Y1") (pin "3") (pinfunction "XTAL_P_3") (pintype "passive"))
    )
    (net (code "56") (name "/XIN-B") (class "Default")
      (node (ref "C73") (pin "1") (pinfunction "1_1") (pintype "passive"))
      (node (ref "U4") (pin "28") (pinfunction "XIN_28") (pintype "passive"))
      (node (ref "Y2") (pin "3") (pinfunction "XTAL_P_3") (pintype "passive"))
    )
    (net (code "57") (name "/XIN-C") (class "Default")
      (node (ref "C95") (pin "1") (pinfunction "1_1") (pintype "passive"))
      (node (ref "U7") (pin "28") (pinfunction "XIN_28") (pintype "passive"))
      (node (ref "Y3") (pin "3") (pinfunction "XTAL_P_3") (pintype "passive"))
    )
    (net (code "58") (name "/XOUT-A") (class "Default")
      (node (ref "C70") (pin "1") (pinfunction "1_1") (pintype "passive"))
      (node (ref "U3") (pin "27") (pinfunction "XOUT_27") (pintype "passive"))
      (node (ref "Y1") (pin "1") (pinfunction "XTAL_N_1") (pintype "passive"))
    )
    (net (code "59") (name "/XOUT-B") (class "Default")
      (node (ref "C72") (pin "1") (pinfunction "1_1") (pintype "passive"))
      (node (ref "U4") (pin "27") (pinfunction "XOUT_27") (pintype "passive"))
      (node (ref "Y2") (pin "1") (pinfunction "XTAL_N_1") (pintype "passive"))
    )
    (net (code "60") (name "/XOUT-C") (class "Default")
      (node (ref "C94") (pin "1") (pinfunction "1_1") (pintype "passive"))
      (node (ref "U7") (pin "27") (pinfunction "XOUT_27") (pintype "passive"))
      (node (ref "Y3") (pin "1") (pinfunction "XTAL_N_1") (pintype "passive"))
    )
    (net (code "67") (name "/cap_SSRX1_N") (class "Default")
      (node (ref "C66") (pin "2") (pinfunction "2_2") (pintype "passive"))
      (node (ref "U3") (pin "19") (pinfunction "SSTXN_19") (pintype "passive"))
    )
    (net (code "68") (name "/cap_SSRX1_P") (class "Default")
      (node (ref "C68") (pin "2") (pinfunction "2_2") (pintype "passive"))
      (node (ref "U3") (pin "20") (pinfunction "SSTXP_20") (pintype "passive"))
    )
    (net (code "69") (name "/cap_SSRX2_N") (class "Default")
      (node (ref "C67") (pin "2") (pinfunction "2_2") (pintype "passive"))
      (node (ref "U4") (pin "19") (pinfunction "SSTXN_19") (pintype "passive"))
    )
    (net (code "70") (name "/cap_SSRX2_P") (class "Default")
      (node (ref "C69") (pin "2") (pinfunction "2_2") (pintype "passive"))
      (node (ref "U4") (pin "20") (pinfunction "SSTXP_20") (pintype "passive"))
    )
    (net (code "71") (name "/cap_SSRX4_N") (class "Default")
      (node (ref "C92") (pin "2") (pinfunction "2_2") (pintype "passive"))
      (node (ref "U7") (pin "19") (pinfunction "SSTXN_19") (pintype "passive"))
    )
    (net (code "72") (name "/cap_SSRX4_P") (class "Default")
      (node (ref "C93") (pin "2") (pinfunction "2_2") (pintype "passive"))
      (node (ref "U7") (pin "20") (pinfunction "SSTXP_20") (pintype "passive"))
    )
    (net (code "79") (name "GND") (class "Default")
      (node (ref "C30") (pin "1") (pinfunction "1_1") (pintype "passive"))
      (node (ref "C31") (pin "1") (pinfunction "1_1") (pintype "passive"))
      (node (ref "C32") (pin "1") (pinfunction "1_1") (pintype "passive"))
      (node (ref "C33") (pin "1") (pinfunction "1_1") (pintype "passive"))
      (node (ref "C34") (pin "1") (pinfunction "1_1") (pintype "passive"))
      (node (ref "C35") (pin "1") (pinfunction "1_1") (pintype "passive"))
      (node (ref "C38") (pin "1") (pinfunction "1_1") (pintype "passive"))
      (node (ref "C39") (pin "1") (pinfunction "1_1") (pintype "passive"))
      (node (ref "C40") (pin "1") (pinfunction "1_1") (pintype "passive"))
      (node (ref "C41") (pin "1") (pinfunction "1_1") (pintype "passive"))
      (node (ref "C42") (pin "1") (pinfunction "1_1") (pintype "passive"))
      (node (ref "C43") (pin "1") (pinfunction "1_1") (pintype "passive"))
      (node (ref "C44") (pin "1") (pinfunction "1_1") (pintype "passive"))
      (node (ref "C45") (pin "1") (pinfunction "1_1") (pintype "passive"))
      (node (ref "C46") (pin "1") (pinfunction "1_1") (pintype "passive"))
      (node (ref "C47") (pin "1") (pinfunction "1_1") (pintype "passive"))
      (node (ref "C48") (pin "1") (pinfunction "1_1") (pintype "passive"))
      (node (ref "C49") (pin "1") (pinfunction "1_1") (pintype "passive"))
      (node (ref "C50") (pin "1") (pinfunction "1_1") (pintype "passive"))
      (node (ref "C51") (pin "1") (pinfunction "1_1") (pintype "passive"))
      (node (ref "C52") (pin "1") (pinfunction "1_1") (pintype "passive"))
      (node (ref "C53") (pin "1") (pinfunction "1_1") (pintype "passive"))
      (node (ref "C54") (pin "1") (pinfunction "1_1") (pintype "passive"))
      (node (ref "C55") (pin "1") (pinfunction "1_1") (pintype "passive"))
      (node (ref "C56") (pin "1") (pinfunction "1_1") (pintype "passive"))
      (node (ref "C57") (pin "1") (pinfunction "1_1") (pintype "passive"))
      (node (ref "C58") (pin "1") (pinfunction "1_1") (pintype "passive"))
      (node (ref "C59") (pin "1") (pinfunction "1_1") (pintype "passive"))
      (node (ref "C60") (pin "1") (pinfunction "1_1") (pintype "passive"))
      (node (ref "C61") (pin "1") (pinfunction "1_1") (pintype "passive"))
      (node (ref "C62") (pin "1") (pinfunction "1_1") (pintype "passive"))
      (node (ref "C63") (pin "1") (pinfunction "1_1") (pintype "passive"))
      (node (ref "C64") (pin "1") (pinfunction "1_1") (pintype "passive"))
      (node (ref "C65") (pin "1") (pinfunction "1_1") (pintype "passive"))
      (node (ref "C70") (pin "2") (pinfunction "2_2") (pintype "passive"))
      (node (ref "C71") (pin "2") (pinfunction "2_2") (pintype "passive"))
      (node (ref "C72") (pin "2") (pinfunction "2_2") (pintype "passive"))
      (node (ref "C73") (pin "2") (pinfunction "2_2") (pintype "passive"))
      (node (ref "C74") (pin "1") (pinfunction "1_1") (pintype "passive"))
      (node (ref "C75") (pin "1") (pinfunction "1_1") (pintype "passive"))
      (node (ref "C76") (pin "1") (pinfunction "1_1") (pintype "passive"))
      (node (ref "C78") (pin "1") (pinfunction "1_1") (pintype "passive"))
      (node (ref "C79") (pin "1") (pinfunction "1_1") (pintype "passive"))
      (node (ref "C80") (pin "1") (pinfunction "1_1") (pintype "passive"))
      (node (ref "C81") (pin "1") (pinfunction "1_1") (pintype "passive"))
      (node (ref "C82") (pin "1") (pinfunction "1_1") (pintype "passive"))
      (node (ref "C83") (pin "1") (pinfunction "1_1") (pintype "passive"))
      (node (ref "C84") (pin "1") (pinfunction "1_1") (pintype "passive"))
      (node (ref "C85") (pin "1") (pinfunction "1_1") (pintype "passive"))
      (node (ref "C86") (pin "1") (pinfunction "1_1") (pintype "passive"))
      (node (ref "C87") (pin "1") (pinfunction "1_1") (pintype "passive"))
      (node (ref "C88") (pin "1") (pinfunction "1_1") (pintype "passive"))
      (node (ref "C89") (pin "1") (pinfunction "1_1") (pintype "passive"))
      (node (ref "C90") (pin "1") (pinfunction "1_1") (pintype "passive"))
      (node (ref "C91") (pin "1") (pinfunction "1_1") (pintype "passive"))
      (node (ref "C94") (pin "2") (pinfunction "2_2") (pintype "passive"))
      (node (ref "C95") (pin "2") (pinfunction "2_2") (pintype "passive"))
      (node (ref "R30") (pin "1") (pinfunction "1_1") (pintype "passive"))
      (node (ref "R31") (pin "1") (pinfunction "1_1") (pintype "passive"))
      (node (ref "R32") (pin "1") (pinfunction "1_1") (pintype "passive"))
      (node (ref "R33") (pin "1") (pinfunction "1_1") (pintype "passive"))
      (node (ref "R36") (pin "1") (pinfunction "1_1") (pintype "passive"))
      (node (ref "R37") (pin "1") (pinfunction "1_1") (pintype "passive"))
      (node (ref "U3") (pin "26") (pinfunction "NC_26") (pintype "passive"))
      (node (ref "U3") (pin "42") (pinfunction "MODE1_42") (pintype "passive"))
      (node (ref "U3") (pin "43") (pinfunction "GND_43") (pintype "passive"))
      (node (ref "U3") (pin "47") (pinfunction "NC_47") (pintype "passive"))
      (node (ref "U3") (pin "49") (pinfunction "EP_49") (pintype "passive"))
      (node (ref "U4") (pin "26") (pinfunction "NC_26") (pintype "passive"))
      (node (ref "U4") (pin "42") (pinfunction "MODE1_42") (pintype "passive"))
      (node (ref "U4") (pin "43") (pinfunction "GND_43") (pintype "passive"))
      (node (ref "U4") (pin "47") (pinfunction "NC_47") (pintype "passive"))
      (node (ref "U4") (pin "49") (pinfunction "EP_49") (pintype "passive"))
      (node (ref "U5") (pin "4") (pinfunction "GND_4") (pintype "passive"))
      (node (ref "U6") (pin "4") (pinfunction "GND_4") (pintype "passive"))
      (node (ref "U7") (pin "26") (pinfunction "NC_26") (pintype "passive"))
      (node (ref "U7") (pin "42") (pinfunction "MODE1_42") (pintype "passive"))
      (node (ref "U7") (pin "43") (pinfunction "GND_43") (pintype "passive"))
      (node (ref "U7") (pin "47") (pinfunction "NC_47") (pintype "passive"))
      (node (ref "U7") (pin "49") (pinfunction "EP_49") (pintype "passive"))
      (node (ref "U8") (pin "4") (pinfunction "GND_4") (pintype "passive"))
      (node (ref "Y1") (pin "2") (pinfunction "GND_2") (pintype "passive"))
      (node (ref "Y1") (pin "4") (pinfunction "GND_4") (pintype "passive"))
      (node (ref "Y2") (pin "2") (pinfunction "GND_2") (pintype "passive"))
      (node (ref "Y2") (pin "4") (pinfunction "GND_4") (pintype "passive"))
      (node (ref "Y3") (pin "2") (pinfunction "GND_2") (pintype "passive"))
      (node (ref "Y3") (pin "4") (pinfunction "GND_4") (pintype "passive"))
    )
    (net (code "80") (name "Net-(U3-RST#)") (class "Default")
      (node (ref "C30") (pin "2") (pinfunction "2_2") (pintype "passive"))
      (node (ref "R26") (pin "2") (pinfunction "2_2") (pintype "passive"))
      (node (ref "U3") (pin "38") (pinfunction "RST#_38") (pintype "passive"))
    )
    (net (code "81") (name "Net-(U3-TEXT)") (class "Default")
      (node (ref "R32") (pin "2") (pinfunction "2_2") (pintype "passive"))
      (node (ref "U3") (pin "36") (pinfunction "TEXT_36") (pintype "passive"))
    )
    (net (code "82") (name "Net-(U3-TME)") (class "Default")
      (node (ref "C36") (pin "1") (pinfunction "1_1") (pintype "passive"))
      (node (ref "R30") (pin "2") (pinfunction "2_2") (pintype "passive"))
      (node (ref "U3") (pin "1") (pinfunction "TME_1") (pintype "passive"))
    )
    (net (code "83") (name "Net-(U3-UAO{slash}GPIO8)") (class "Default")
      (node (ref "R28") (pin "2") (pinfunction "2_2") (pintype "passive"))
      (node (ref "U3") (pin "37") (pinfunction "UAO/GPIO8_37") (pintype "passive"))
    )
    (net (code "84") (name "Net-(U4-RST#)") (class "Default")
      (node (ref "C31") (pin "2") (pinfunction "2_2") (pintype "passive"))
      (node (ref "R27") (pin "2") (pinfunction "2_2") (pintype "passive"))
      (node (ref "U4") (pin "38") (pinfunction "RST#_38") (pintype "passive"))
    )
    (net (code "85") (name "Net-(U4-TEXT)") (class "Default")
      (node (ref "R33") (pin "2") (pinfunction "2_2") (pintype "passive"))
      (node (ref "U4") (pin "36") (pinfunction "TEXT_36") (pintype "passive"))
    )
    (net (code "86") (name "Net-(U4-TME)") (class "Default")
      (node (ref "C37") (pin "1") (pinfunction "1_1") (pintype "passive"))
      (node (ref "R31") (pin "2") (pinfunction "2_2") (pintype "passive"))
      (node (ref "U4") (pin "1") (pinfunction "TME_1") (pintype "passive"))
    )
    (net (code "87") (name "Net-(U4-UAO{slash}GPIO8)") (class "Default")
      (node (ref "R29") (pin "2") (pinfunction "2_2") (pintype "passive"))
      (node (ref "U4") (pin "37") (pinfunction "UAO/GPIO8_37") (pintype "passive"))
    )
    (net (code "88") (name "Net-(U7-RST#)") (class "Default")
      (node (ref "C74") (pin "2") (pinfunction "2_2") (pintype "passive"))
      (node (ref "R34") (pin "2") (pinfunction "2_2") (pintype "passive"))
      (node (ref "U7") (pin "38") (pinfunction "RST#_38") (pintype "passive"))
    )
    (net (code "89") (name "Net-(U7-TEXT)") (class "Default")
      (node (ref "R37") (pin "2") (pinfunction "2_2") (pintype "passive"))
      (node (ref "U7") (pin "36") (pinfunction "TEXT_36") (pintype "passive"))
    )
    (net (code "90") (name "Net-(U7-TME)") (class "Default")
      (node (ref "C77") (pin "1") (pinfunction "1_1") (pintype "passive"))
      (node (ref "R36") (pin "2") (pinfunction "2_2") (pintype "passive"))
      (node (ref "U7") (pin "1") (pinfunction "TME_1") (pintype "passive"))
    )
    (net (code "91") (name "Net-(U7-UAO{slash}GPIO8)") (class "Default")
      (node (ref "R35") (pin "2") (pinfunction "2_2") (pintype "passive"))
      (node (ref "U7") (pin "37") (pinfunction "UAO/GPIO8_37") (pintype "passive"))
    )
    (net (code "92") (name "VBUS") (class "Default")
      (node (ref "C54") (pin "2") (pinfunction "2_2") (pintype "passive"))
      (node (ref "C55") (pin "2") (pinfunction "2_2") (pintype "passive"))
      (node (ref "C60") (pin "2") (pinfunction "2_2") (pintype "passive"))
      (node (ref "C61") (pin "2") (pinfunction "2_2") (pintype "passive"))
      (node (ref "C86") (pin "2") (pinfunction "2_2") (pintype "passive"))
      (node (ref "C87") (pin "2") (pinfunction "2_2") (pintype "passive"))
      (node (ref "U3") (pin "12") (pinfunction "VBUS_12") (pintype "passive"))
      (node (ref "U3") (pin "45") (pinfunction "VREG_IN_45") (pintype "passive"))
      (node (ref "U4") (pin "12") (pinfunction "VBUS_12") (pintype "passive"))
      (node (ref "U4") (pin "45") (pinfunction "VREG_IN_45") (pintype "passive"))
      (node (ref "U7") (pin "12") (pinfunction "VBUS_12") (pintype "passive"))
      (node (ref "U7") (pin "45") (pinfunction "VREG_IN_45") (pintype "passive"))
    )
    (net (code "93") (name "VCC1V2-A") (class "Default")
      (node (ref "C32") (pin "2") (pinfunction "2_2") (pintype "passive"))
      (node (ref "C33") (pin "2") (pinfunction "2_2") (pintype "passive"))
      (node (ref "C38") (pin "2") (pinfunction "2_2") (pintype "passive"))
      (node (ref "C39") (pin "2") (pinfunction "2_2") (pintype "passive"))
      (node (ref "C40") (pin "2") (pinfunction "2_2") (pintype "passive"))
      (node (ref "C41") (pin "2") (pinfunction "2_2") (pintype "passive"))
      (node (ref "C42") (pin "2") (pinfunction "2_2") (pintype "passive"))
      (node (ref "C43") (pin "2") (pinfunction "2_2") (pintype "passive"))
      (node (ref "C44") (pin "2") (pinfunction "2_2") (pintype "passive"))
      (node (ref "C45") (pin "2") (pinfunction "2_2") (pintype "passive"))
      (node (ref "L4") (pin "2") (pinfunction "2_2") (pintype "passive"))
      (node (ref "U3") (pin "10") (pinfunction "VCC12_10") (pintype "passive"))
      (node (ref "U3") (pin "18") (pinfunction "VCC12_18") (pintype "passive"))
      (node (ref "U3") (pin "21") (pinfunction "VCC12_21") (pintype "passive"))
      (node (ref "U3") (pin "24") (pinfunction "VCC12_24") (pintype "passive"))
      (node (ref "U3") (pin "29") (pinfunction "VCC12_29") (pintype "passive"))
      (node (ref "U3") (pin "32") (pinfunction "VCC12_32") (pintype "passive"))
      (node (ref "U3") (pin "4") (pinfunction "VCC12_4") (pintype "passive"))
      (node (ref "U3") (pin "40") (pinfunction "VCC12_40") (pintype "passive"))
    )
    (net (code "94") (name "VCC1V2-B") (class "Default")
      (node (ref "C34") (pin "2") (pinfunction "2_2") (pintype "passive"))
      (node (ref "C35") (pin "2") (pinfunction "2_2") (pintype "passive"))
      (node (ref "C46") (pin "2") (pinfunction "2_2") (pintype "passive"))
      (node (ref "C47") (pin "2") (pinfunction "2_2") (pintype "passive"))
      (node (ref "C48") (pin "2") (pinfunction "2_2") (pintype "passive"))
      (node (ref "C49") (pin "2") (pinfunction "2_2") (pintype "passive"))
      (node (ref "C50") (pin "2") (pinfunction "2_2") (pintype "passive"))
      (node (ref "C51") (pin "2") (pinfunction "2_2") (pintype "passive"))
      (node (ref "C52") (pin "2") (pinfunction "2_2") (pintype "passive"))
      (node (ref "C53") (pin "2") (pinfunction "2_2") (pintype "passive"))
      (node (ref "L5") (pin "2") (pinfunction "2_2") (pintype "passive"))
      (node (ref "U4") (pin "10") (pinfunction "VCC12_10") (pintype "passive"))
      (node (ref "U4") (pin "18") (pinfunction "VCC12_18") (pintype "passive"))
      (node (ref "U4") (pin "21") (pinfunction "VCC12_21") (pintype "passive"))
      (node (ref "U4") (pin "24") (pinfunction "VCC12_24") (pintype "passive"))
      (node (ref "U4") (pin "29") (pinfunction "VCC12_29") (pintype "passive"))
      (node (ref "U4") (pin "32") (pinfunction "VCC12_32") (pintype "passive"))
      (node (ref "U4") (pin "4") (pinfunction "VCC12_4") (pintype "passive"))
      (node (ref "U4") (pin "40") (pinfunction "VCC12_40") (pintype "passive"))
    )
    (net (code "95") (name "VCC1V2-C") (class "Default")
      (node (ref "C75") (pin "2") (pinfunction "2_2") (pintype "passive"))
      (node (ref "C76") (pin "2") (pinfunction "2_2") (pintype "passive"))
      (node (ref "C78") (pin "2") (pinfunction "2_2") (pintype "passive"))
      (node (ref "C79") (pin "2") (pinfunction "2_2") (pintype "passive"))
      (node (ref "C80") (pin "2") (pinfunction "2_2") (pintype "passive"))
      (node (ref "C81") (pin "2") (pinfunction "2_2") (pintype "passive"))
      (node (ref "C82") (pin "2") (pinfunction "2_2") (pintype "passive"))
      (node (ref "C83") (pin "2") (pinfunction "2_2") (pintype "passive"))
      (node (ref "C84") (pin "2") (pinfunction "2_2") (pintype "passive"))
      (node (ref "C85") (pin "2") (pinfunction "2_2") (pintype "passive"))
      (node (ref "L6") (pin "2") (pinfunction "2_2") (pintype "passive"))
      (node (ref "U7") (pin "10") (pinfunction "VCC12_10") (pintype "passive"))
      (node (ref "U7") (pin "18") (pinfunction "VCC12_18") (pintype "passive"))
      (node (ref "U7") (pin "21") (pinfunction "VCC12_21") (pintype "passive"))
      (node (ref "U7") (pin "24") (pinfunction "VCC12_24") (pintype "passive"))
      (node (ref "U7") (pin "29") (pinfunction "VCC12_29") (pintype "passive"))
      (node (ref "U7") (pin "32") (pinfunction "VCC12_32") (pintype "passive"))
      (node (ref "U7") (pin "4") (pinfunction "VCC12_4") (pintype "passive"))
      (node (ref "U7") (pin "40") (pinfunction "VCC12_40") (pintype "passive"))
    )
    (net (code "96") (name "VCC3V3-A") (class "Default")
      (node (ref "C36") (pin "2") (pinfunction "2_2") (pintype "passive"))
      (node (ref "C56") (pin "2") (pinfunction "2_2") (pintype "passive"))
      (node (ref "C57") (pin "2") (pinfunction "2_2") (pintype "passive"))
      (node (ref "C58") (pin "2") (pinfunction "2_2") (pintype "passive"))
      (node (ref "C59") (pin "2") (pinfunction "2_2") (pintype "passive"))
      (node (ref "R26") (pin "1") (pinfunction "1_1") (pintype "passive"))
      (node (ref "R28") (pin "1") (pinfunction "1_1") (pintype "passive"))
      (node (ref "U3") (pin "14") (pinfunction "VCC33_14") (pintype "passive"))
      (node (ref "U3") (pin "39") (pinfunction "VCC33_39") (pintype "passive"))
      (node (ref "U3") (pin "46") (pinfunction "MODE0_46") (pintype "passive"))
      (node (ref "U3") (pin "7") (pinfunction "VCC33_7") (pintype "passive"))
      (node (ref "U5") (pin "3") (pinfunction "WP#_3") (pintype "passive"))
      (node (ref "U5") (pin "7") (pinfunction "HOLD#_7") (pintype "passive"))
      (node (ref "U5") (pin "8") (pinfunction "VCC_8") (pintype "passive"))
    )
    (net (code "97") (name "VCC3V3-B") (class "Default")
      (node (ref "C37") (pin "2") (pinfunction "2_2") (pintype "passive"))
      (node (ref "C62") (pin "2") (pinfunction "2_2") (pintype "passive"))
      (node (ref "C63") (pin "2") (pinfunction "2_2") (pintype "passive"))
      (node (ref "C64") (pin "2") (pinfunction "2_2") (pintype "passive"))
      (node (ref "C65") (pin "2") (pinfunction "2_2") (pintype "passive"))
      (node (ref "R27") (pin "1") (pinfunction "1_1") (pintype "passive"))
      (node (ref "R29") (pin "1") (pinfunction "1_1") (pintype "passive"))
      (node (ref "U4") (pin "14") (pinfunction "VCC33_14") (pintype "passive"))
      (node (ref "U4") (pin "39") (pinfunction "VCC33_39") (pintype "passive"))
      (node (ref "U4") (pin "46") (pinfunction "MODE0_46") (pintype "passive"))
      (node (ref "U4") (pin "7") (pinfunction "VCC33_7") (pintype "passive"))
      (node (ref "U6") (pin "3") (pinfunction "WP#_3") (pintype "passive"))
      (node (ref "U6") (pin "7") (pinfunction "HOLD#_7") (pintype "passive"))
      (node (ref "U6") (pin "8") (pinfunction "VCC_8") (pintype "passive"))
    )
    (net (code "98") (name "VCC3V3-C") (class "Default")
      (node (ref "C77") (pin "2") (pinfunction "2_2") (pintype "passive"))
      (node (ref "C88") (pin "2") (pinfunction "2_2") (pintype "passive"))
      (node (ref "C89") (pin "2") (pinfunction "2_2") (pintype "passive"))
      (node (ref "C90") (pin "2") (pinfunction "2_2") (pintype "passive"))
      (node (ref "C91") (pin "2") (pinfunction "2_2") (pintype "passive"))
      (node (ref "R34") (pin "1") (pinfunction "1_1") (pintype "passive"))
      (node (ref "R35") (pin "1") (pinfunction "1_1") (pintype "passive"))
      (node (ref "U7") (pin "14") (pinfunction "VCC33_14") (pintype "passive"))
      (node (ref "U7") (pin "39") (pinfunction "VCC33_39") (pintype "passive"))
      (node (ref "U7") (pin "46") (pinfunction "MODE0_46") (pintype "passive"))
      (node (ref "U7") (pin "7") (pinfunction "VCC33_7") (pintype "passive"))
      (node (ref "U8") (pin "3") (pinfunction "WP#_3") (pintype "passive"))
      (node (ref "U8") (pin "7") (pinfunction "HOLD#_7") (pintype "passive"))
      (node (ref "U8") (pin "8") (pinfunction "VCC_8") (pintype "passive"))
    )
    (net (code "99") (name "unconnected-(U3-GPIO7-Pad41)") (class "Default")
      (node (ref "U3") (pin "41") (pinfunction "GPIO7_41") (pintype "passive+no_connect"))
    )
    (net (code "100") (name "unconnected-(U3-GPIO9-Pad48)") (class "Default")
      (node (ref "U3") (pin "48") (pinfunction "GPIO9_48") (pintype "passive+no_connect"))
    )
    (net (code "101") (name "unconnected-(U3-NC-Pad16)") (class "Default")
      (node (ref "U3") (pin "16") (pinfunction "NC_16") (pintype "passive+no_connect"))
    )
    (net (code "102") (name "unconnected-(U3-NC-Pad17)") (class "Default")
      (node (ref "U3") (pin "17") (pinfunction "NC_17") (pintype "passive+no_connect"))
    )
    (net (code "103") (name "unconnected-(U3-NC-Pad25)") (class "Default")
      (node (ref "U3") (pin "25") (pinfunction "NC_25") (pintype "passive+no_connect"))
    )
    (net (code "104") (name "unconnected-(U3-NC-Pad35)") (class "Default")
      (node (ref "U3") (pin "35") (pinfunction "NC_35") (pintype "passive+no_connect"))
    )
    (net (code "105") (name "unconnected-(U4-GPIO7-Pad41)") (class "Default")
      (node (ref "U4") (pin "41") (pinfunction "GPIO7_41") (pintype "passive+no_connect"))
    )
    (net (code "106") (name "unconnected-(U4-GPIO9-Pad48)") (class "Default")
      (node (ref "U4") (pin "48") (pinfunction "GPIO9_48") (pintype "passive+no_connect"))
    )
    (net (code "107") (name "unconnected-(U4-NC-Pad16)") (class "Default")
      (node (ref "U4") (pin "16") (pinfunction "NC_16") (pintype "passive+no_connect"))
    )
    (net (code "108") (name "unconnected-(U4-NC-Pad17)") (class "Default")
      (node (ref "U4") (pin "17") (pinfunction "NC_17") (pintype "passive+no_connect"))
    )
    (net (code "109") (name "unconnected-(U4-NC-Pad25)") (class "Default")
      (node (ref "U4") (pin "25") (pinfunction "NC_25") (pintype "passive+no_connect"))
    )
    (net (code "110") (name "unconnected-(U4-NC-Pad35)") (class "Default")
      (node (ref "U4") (pin "35") (pinfunction "NC_35") (pintype "passive+no_connect"))
    )
    (net (code "111") (name "unconnected-(U7-GPIO7-Pad41)") (class "Default")
      (node (ref "U7") (pin "41") (pinfunction "GPIO7_41") (pintype "passive+no_connect"))
    )
    (net (code "112") (name "unconnected-(U7-GPIO9-Pad48)") (class "Default")
      (node (ref "U7") (pin "48") (pinfunction "GPIO9_48") (pintype "passive+no_connect"))
    )
    (net (code "113") (name "unconnected-(U7-NC-Pad16)") (class "Default")
      (node (ref "U7") (pin "16") (pinfunction "NC_16") (pintype "passive+no_connect"))
    )
    (net (code "114") (name "unconnected-(U7-NC-Pad17)") (class "Default")
      (node (ref "U7") (pin "17") (pinfunction "NC_17") (pintype "passive+no_connect"))
    )
    (net (code "115") (name "unconnected-(U7-NC-Pad25)") (class "Default")
      (node (ref "U7") (pin "25") (pinfunction "NC_25") (pintype "passive+no_connect"))
    )
    (net (code "116") (name "unconnected-(U7-NC-Pad35)") (class "Default")
      (node (ref "U7") (pin "35") (pinfunction "NC_35") (pintype "passive+no_connect"))
    )
  )
)
